# Sensor_HallArray_Ctrl.net
KiCad netlist of a schematic drawn in EAGLE
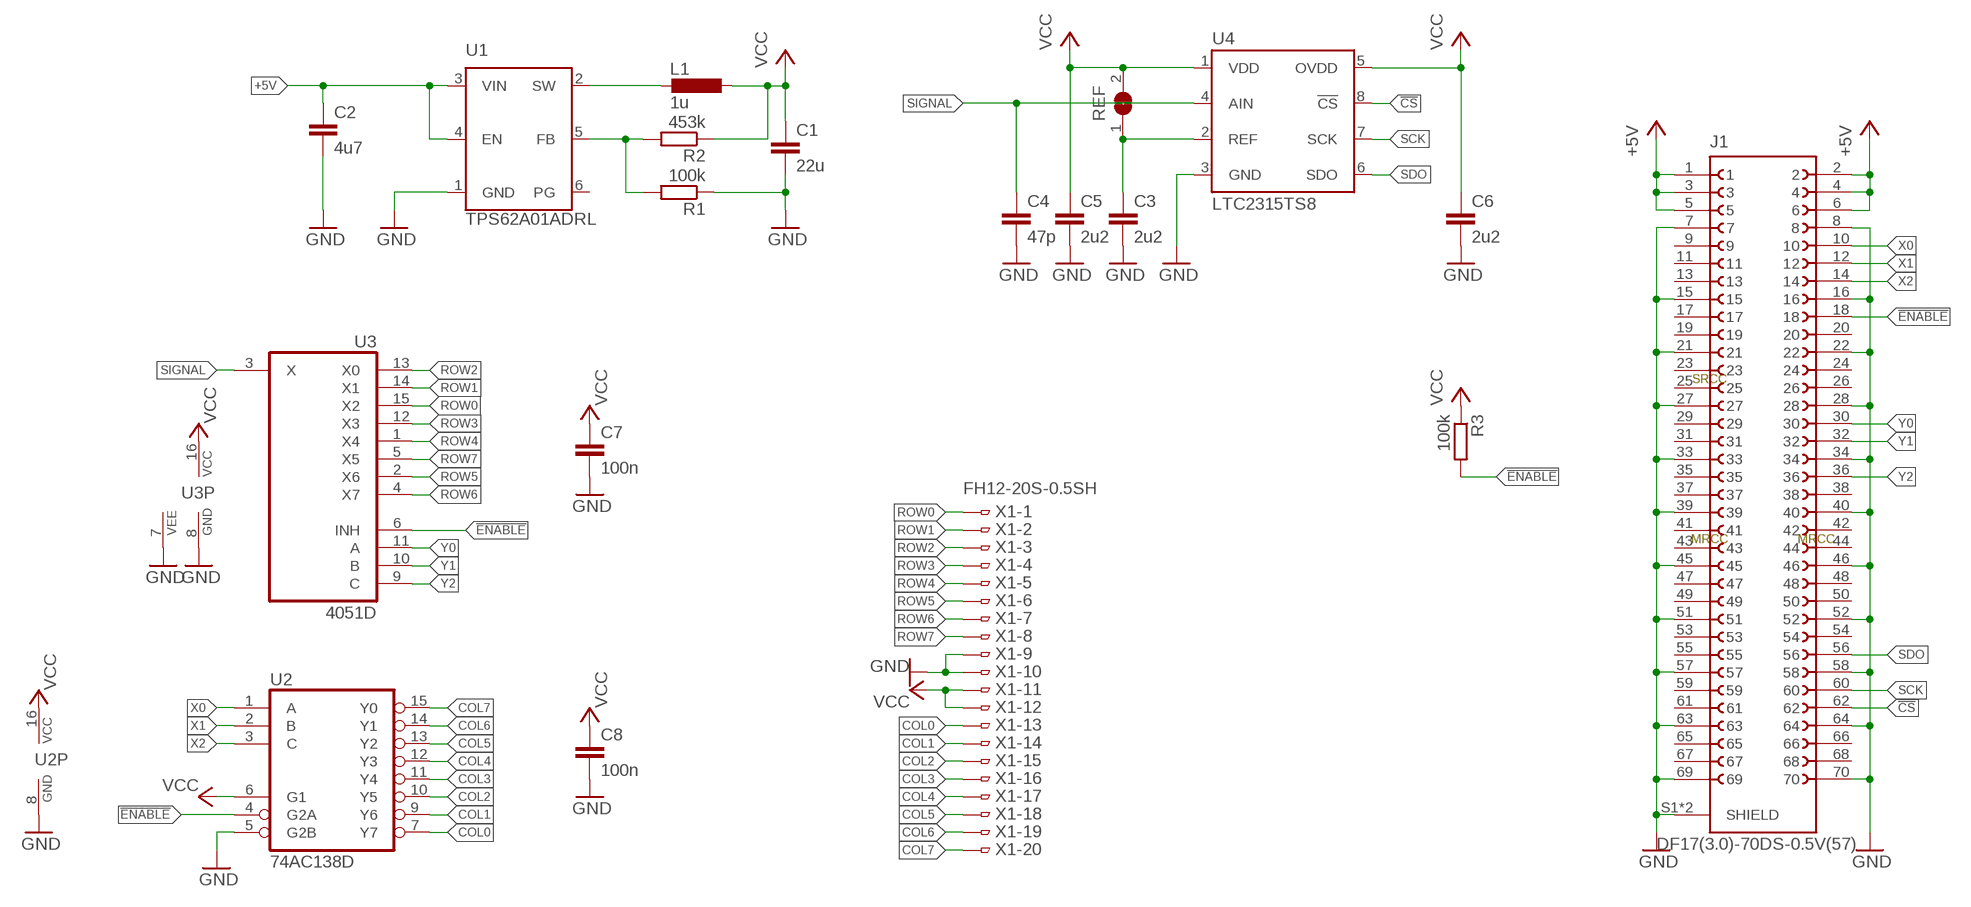
[diagram p0: schematic, sheet 1]

(export (version "E")
  (design (tool "Eeschema 10.0.6"))
  (components
    (comp (ref "C1")
      (value "22u")
      (footprint "eagle-import:C0603")
      (libsource (lib "eagle-import") (part "C-EUC0603"))
    )
    (comp (ref "C2")
      (value "4u7")
      (footprint "eagle-import:C0603")
      (libsource (lib "eagle-import") (part "C-EUC0603"))
    )
    (comp (ref "C3")
      (value "2u2")
      (footprint "eagle-import:C0603")
      (libsource (lib "eagle-import") (part "C-EUC0603"))
    )
    (comp (ref "C4")
      (value "47p")
      (footprint "eagle-import:C0402")
      (libsource (lib "eagle-import") (part "rcl_334_C-EUC0402"))
    )
    (comp (ref "C5")
      (value "2u2")
      (footprint "eagle-import:C0603")
      (libsource (lib "eagle-import") (part "C-EUC0603"))
    )
    (comp (ref "C6")
      (value "2u2")
      (footprint "eagle-import:C0603")
      (libsource (lib "eagle-import") (part "C-EUC0603"))
    )
    (comp (ref "C7")
      (value "100n")
      (footprint "eagle-import:C0402")
      (libsource (lib "eagle-import") (part "rcl_334_C-EUC0402"))
    )
    (comp (ref "C8")
      (value "100n")
      (footprint "eagle-import:C0402")
      (libsource (lib "eagle-import") (part "rcl_334_C-EUC0402"))
    )
    (comp (ref "J1")
      (value "DF17(3.0)-70DS-0.5V(57)")
      (footprint "eagle-import:DF17(3.0)-70DS-0.5V(57)")
      (libsource (lib "eagle-import") (part "DF17(3.0)-70DS-0.5V(57)"))
    )
    (comp (ref "L1")
      (value "1u")
      (footprint "eagle-import:L1008")
      (fields (field (name "MPN") "LQM2HPN1R0MG0L"))
      (libsource (lib "eagle-import") (part "L-EU1008"))
    )
    (comp (ref "R1")
      (value "100k")
      (footprint "eagle-import:R0402")
      (libsource (lib "eagle-import") (part "R-EU_R0402"))
    )
    (comp (ref "R2")
      (value "453k")
      (footprint "eagle-import:R0402")
      (libsource (lib "eagle-import") (part "R-EU_R0402"))
    )
    (comp (ref "R3")
      (value "100k")
      (footprint "eagle-import:R0402")
      (libsource (lib "eagle-import") (part "R-EU_R0402"))
    )
    (comp (ref "REF") (value "SJ") (footprint "eagle-import:SJ") (libsource (lib "eagle-import") (part "SJ")))
    (comp (ref "U1")
      (value "TPS62A01ADRL")
      (footprint "eagle-import:SOTFL50P160X60-6N")
      (fields (field (name "MANUFACTURER_PART_NUMBER") "TPS62A01ADRLR"))
      (libsource (lib "eagle-import") (part "TPS62A01ADRL"))
    )
    (comp (ref "U2")
      (value "74AC138D")
      (footprint "eagle-import:SO16")
      (libsource (lib "eagle-import") (part "74138DAC"))
    )
    (comp (ref "U3")
      (value "4051D")
      (footprint "eagle-import:SO16")
      (libsource (lib "eagle-import") (part "4051D"))
    )
    (comp (ref "U4")
      (value "LTC2315TS8")
      (footprint "eagle-import:SOT23-8L")
      (libsource (lib "eagle-import") (part "LTC2315TS8"))
    )
    (comp (ref "X1")
      (value "FH12-20S-0.5SH")
      (footprint "eagle-import:FH12-20S-0.5SH")
      (fields (field (name "MPN") "FH12-20S-0.5SH(55)"))
      (libsource (lib "eagle-import") (part "FH12-20S-0.5SH"))
    )
  )
  (nets
    (net (code "1") (name "+5V") (class "Default")
      (node (ref "C2") (pin "1") (pinfunction "1_1") (pintype "passive"))
      (node (ref "J1") (pin "1") (pinfunction "1_1") (pintype "passive"))
      (node (ref "J1") (pin "2") (pinfunction "2_2") (pintype "passive"))
      (node (ref "J1") (pin "3") (pinfunction "3_3") (pintype "passive"))
      (node (ref "J1") (pin "4") (pinfunction "4_4") (pintype "passive"))
      (node (ref "J1") (pin "5") (pinfunction "5_5") (pintype "passive"))
      (node (ref "J1") (pin "6") (pinfunction "6_6") (pintype "passive"))
      (node (ref "U1") (pin "3") (pinfunction "VIN_3") (pintype "bidirectional"))
      (node (ref "U1") (pin "4") (pinfunction "EN_4") (pintype "bidirectional"))
    )
    (net (code "2") (name "/~{CS}") (class "Default")
      (node (ref "J1") (pin "62") (pinfunction "62_62") (pintype "passive"))
      (node (ref "U4") (pin "8") (pinfunction "~{CS}_8") (pintype "input"))
    )
    (net (code "3") (name "/~{ENABLE}") (class "Default")
      (node (ref "J1") (pin "18") (pinfunction "18_18") (pintype "passive"))
      (node (ref "R3") (pin "2") (pinfunction "2_2") (pintype "passive"))
      (node (ref "U2") (pin "4") (pinfunction "G2A_4") (pintype "input"))
      (node (ref "U3") (pin "6") (pinfunction "INH_6") (pintype "input"))
    )
    (net (code "4") (name "COL0") (class "Default")
      (node (ref "U2") (pin "7") (pinfunction "Y7_7") (pintype "output"))
      (node (ref "X1") (pin "13") (pinfunction "1_13") (pintype "passive"))
    )
    (net (code "5") (name "COL1") (class "Default")
      (node (ref "U2") (pin "9") (pinfunction "Y6_9") (pintype "output"))
      (node (ref "X1") (pin "14") (pinfunction "1_14") (pintype "passive"))
    )
    (net (code "6") (name "COL2") (class "Default")
      (node (ref "U2") (pin "10") (pinfunction "Y5_10") (pintype "output"))
      (node (ref "X1") (pin "15") (pinfunction "1_15") (pintype "passive"))
    )
    (net (code "7") (name "COL3") (class "Default")
      (node (ref "U2") (pin "11") (pinfunction "Y4_11") (pintype "output"))
      (node (ref "X1") (pin "16") (pinfunction "1_16") (pintype "passive"))
    )
    (net (code "8") (name "COL4") (class "Default")
      (node (ref "U2") (pin "12") (pinfunction "Y3_12") (pintype "output"))
      (node (ref "X1") (pin "17") (pinfunction "1_17") (pintype "passive"))
    )
    (net (code "9") (name "COL5") (class "Default")
      (node (ref "U2") (pin "13") (pinfunction "Y2_13") (pintype "output"))
      (node (ref "X1") (pin "18") (pinfunction "1_18") (pintype "passive"))
    )
    (net (code "10") (name "COL6") (class "Default")
      (node (ref "U2") (pin "14") (pinfunction "Y1_14") (pintype "output"))
      (node (ref "X1") (pin "19") (pinfunction "1_19") (pintype "passive"))
    )
    (net (code "11") (name "COL7") (class "Default")
      (node (ref "U2") (pin "15") (pinfunction "Y0_15") (pintype "output"))
      (node (ref "X1") (pin "20") (pinfunction "1_20") (pintype "passive"))
    )
    (net (code "12") (name "GND") (class "Default")
      (node (ref "C1") (pin "2") (pinfunction "2_2") (pintype "passive"))
      (node (ref "C2") (pin "2") (pinfunction "2_2") (pintype "passive"))
      (node (ref "C3") (pin "2") (pinfunction "2_2") (pintype "passive"))
      (node (ref "C4") (pin "2") (pinfunction "2_2") (pintype "passive"))
      (node (ref "C5") (pin "2") (pinfunction "2_2") (pintype "passive"))
      (node (ref "C6") (pin "2") (pinfunction "2_2") (pintype "passive"))
      (node (ref "C7") (pin "2") (pinfunction "2_2") (pintype "passive"))
      (node (ref "C8") (pin "2") (pinfunction "2_2") (pintype "passive"))
      (node (ref "J1") (pin "15") (pinfunction "15_15") (pintype "passive"))
      (node (ref "J1") (pin "16") (pinfunction "16_16") (pintype "passive"))
      (node (ref "J1") (pin "21") (pinfunction "21_21") (pintype "passive"))
      (node (ref "J1") (pin "22") (pinfunction "22_22") (pintype "passive"))
      (node (ref "J1") (pin "27") (pinfunction "27_27") (pintype "passive"))
      (node (ref "J1") (pin "28") (pinfunction "28_28") (pintype "passive"))
      (node (ref "J1") (pin "33") (pinfunction "33_33") (pintype "passive"))
      (node (ref "J1") (pin "34") (pinfunction "34_34") (pintype "passive"))
      (node (ref "J1") (pin "39") (pinfunction "39_39") (pintype "passive"))
      (node (ref "J1") (pin "40") (pinfunction "40_40") (pintype "passive"))
      (node (ref "J1") (pin "45") (pinfunction "45_45") (pintype "passive"))
      (node (ref "J1") (pin "46") (pinfunction "46_46") (pintype "passive"))
      (node (ref "J1") (pin "51") (pinfunction "51_51") (pintype "passive"))
      (node (ref "J1") (pin "52") (pinfunction "52_52") (pintype "passive"))
      (node (ref "J1") (pin "57") (pinfunction "57_57") (pintype "passive"))
      (node (ref "J1") (pin "58") (pinfunction "58_58") (pintype "passive"))
      (node (ref "J1") (pin "63") (pinfunction "63_63") (pintype "passive"))
      (node (ref "J1") (pin "64") (pinfunction "64_64") (pintype "passive"))
      (node (ref "J1") (pin "69") (pinfunction "69_69") (pintype "passive"))
      (node (ref "J1") (pin "7") (pinfunction "7_7") (pintype "passive"))
      (node (ref "J1") (pin "70") (pinfunction "70_70") (pintype "passive"))
      (node (ref "J1") (pin "8") (pinfunction "8_8") (pintype "passive"))
      (node (ref "J1") (pin "S1") (pinfunction "SHIELD_S1") (pintype "passive"))
      (node (ref "J1") (pin "S2") (pinfunction "SHIELD_S2") (pintype "passive"))
      (node (ref "R1") (pin "1") (pinfunction "1_1") (pintype "passive"))
      (node (ref "U1") (pin "1") (pinfunction "GND_1") (pintype "bidirectional"))
      (node (ref "U2") (pin "5") (pinfunction "G2B_5") (pintype "input"))
      (node (ref "U2") (pin "8") (pinfunction "GND_8") (pintype "power_in"))
      (node (ref "U3") (pin "7") (pinfunction "VEE_7") (pintype "power_in"))
      (node (ref "U3") (pin "8") (pinfunction "GND_8") (pintype "power_in"))
      (node (ref "U4") (pin "3") (pinfunction "GND_3") (pintype "power_in"))
      (node (ref "X1") (pin "10") (pinfunction "1_10") (pintype "passive"))
      (node (ref "X1") (pin "9") (pinfunction "1_9") (pintype "passive"))
    )
    (net (code "13") (name "Net-(U1-FB)") (class "Default")
      (node (ref "R1") (pin "2") (pinfunction "2_2") (pintype "passive"))
      (node (ref "R2") (pin "2") (pinfunction "2_2") (pintype "passive"))
      (node (ref "U1") (pin "5") (pinfunction "FB_5") (pintype "bidirectional"))
    )
    (net (code "14") (name "Net-(U1-SW)") (class "Default")
      (node (ref "L1") (pin "2") (pinfunction "2_2") (pintype "passive"))
      (node (ref "U1") (pin "2") (pinfunction "SW_2") (pintype "bidirectional"))
    )
    (net (code "15") (name "Net-(U4-REF)") (class "Default")
      (node (ref "C3") (pin "1") (pinfunction "1_1") (pintype "passive"))
      (node (ref "REF") (pin "1") (pinfunction "1_1") (pintype "passive"))
      (node (ref "U4") (pin "2") (pinfunction "REF_2") (pintype "input"))
    )
    (net (code "16") (name "ROW0") (class "Default")
      (node (ref "U3") (pin "15") (pinfunction "X2_15") (pintype "bidirectional"))
      (node (ref "X1") (pin "1") (pinfunction "1_1") (pintype "passive"))
    )
    (net (code "17") (name "ROW1") (class "Default")
      (node (ref "U3") (pin "14") (pinfunction "X1_14") (pintype "bidirectional"))
      (node (ref "X1") (pin "2") (pinfunction "1_2") (pintype "passive"))
    )
    (net (code "18") (name "ROW2") (class "Default")
      (node (ref "U3") (pin "13") (pinfunction "X0_13") (pintype "bidirectional"))
      (node (ref "X1") (pin "3") (pinfunction "1_3") (pintype "passive"))
    )
    (net (code "19") (name "ROW3") (class "Default")
      (node (ref "U3") (pin "12") (pinfunction "X3_12") (pintype "bidirectional"))
      (node (ref "X1") (pin "4") (pinfunction "1_4") (pintype "passive"))
    )
    (net (code "20") (name "ROW4") (class "Default")
      (node (ref "U3") (pin "1") (pinfunction "X4_1") (pintype "bidirectional"))
      (node (ref "X1") (pin "5") (pinfunction "1_5") (pintype "passive"))
    )
    (net (code "21") (name "ROW5") (class "Default")
      (node (ref "U3") (pin "2") (pinfunction "X6_2") (pintype "bidirectional"))
      (node (ref "X1") (pin "6") (pinfunction "1_6") (pintype "passive"))
    )
    (net (code "22") (name "ROW6") (class "Default")
      (node (ref "U3") (pin "4") (pinfunction "X7_4") (pintype "bidirectional"))
      (node (ref "X1") (pin "7") (pinfunction "1_7") (pintype "passive"))
    )
    (net (code "23") (name "ROW7") (class "Default")
      (node (ref "U3") (pin "5") (pinfunction "X5_5") (pintype "bidirectional"))
      (node (ref "X1") (pin "8") (pinfunction "1_8") (pintype "passive"))
    )
    (net (code "24") (name "SCK") (class "Default")
      (node (ref "J1") (pin "60") (pinfunction "60_60") (pintype "passive"))
      (node (ref "U4") (pin "7") (pinfunction "SCK_7") (pintype "input"))
    )
    (net (code "25") (name "SDO") (class "Default")
      (node (ref "J1") (pin "56") (pinfunction "56_56") (pintype "passive"))
      (node (ref "U4") (pin "6") (pinfunction "SDO_6") (pintype "output"))
    )
    (net (code "26") (name "SIGNAL") (class "Default")
      (node (ref "C4") (pin "1") (pinfunction "1_1") (pintype "passive"))
      (node (ref "U3") (pin "3") (pinfunction "X_3") (pintype "bidirectional"))
      (node (ref "U4") (pin "4") (pinfunction "AIN_4") (pintype "input"))
    )
    (net (code "27") (name "VCC") (class "Default")
      (node (ref "C1") (pin "1") (pinfunction "1_1") (pintype "passive"))
      (node (ref "C5") (pin "1") (pinfunction "1_1") (pintype "passive"))
      (node (ref "C6") (pin "1") (pinfunction "1_1") (pintype "passive"))
      (node (ref "C7") (pin "1") (pinfunction "1_1") (pintype "passive"))
      (node (ref "C8") (pin "1") (pinfunction "1_1") (pintype "passive"))
      (node (ref "L1") (pin "1") (pinfunction "1_1") (pintype "passive"))
      (node (ref "R2") (pin "1") (pinfunction "1_1") (pintype "passive"))
      (node (ref "R3") (pin "1") (pinfunction "1_1") (pintype "passive"))
      (node (ref "REF") (pin "2") (pinfunction "2_2") (pintype "passive"))
      (node (ref "U2") (pin "16") (pinfunction "VCC_16") (pintype "power_in"))
      (node (ref "U2") (pin "6") (pinfunction "G1_6") (pintype "input"))
      (node (ref "U3") (pin "16") (pinfunction "VCC_16") (pintype "power_in"))
      (node (ref "U4") (pin "1") (pinfunction "VDD_1") (pintype "power_in"))
      (node (ref "U4") (pin "5") (pinfunction "OVDD_5") (pintype "power_in"))
      (node (ref "X1") (pin "11") (pinfunction "1_11") (pintype "passive"))
      (node (ref "X1") (pin "12") (pinfunction "1_12") (pintype "passive"))
    )
    (net (code "28") (name "X0") (class "Default")
      (node (ref "J1") (pin "10") (pinfunction "10_10") (pintype "passive"))
      (node (ref "U2") (pin "1") (pinfunction "A_1") (pintype "input"))
    )
    (net (code "29") (name "X1") (class "Default")
      (node (ref "J1") (pin "12") (pinfunction "12_12") (pintype "passive"))
      (node (ref "U2") (pin "2") (pinfunction "B_2") (pintype "input"))
    )
    (net (code "30") (name "X2") (class "Default")
      (node (ref "J1") (pin "14") (pinfunction "14_14") (pintype "passive"))
      (node (ref "U2") (pin "3") (pinfunction "C_3") (pintype "input"))
    )
    (net (code "31") (name "Y0") (class "Default")
      (node (ref "J1") (pin "30") (pinfunction "30_30") (pintype "passive"))
      (node (ref "U3") (pin "11") (pinfunction "A_11") (pintype "input"))
    )
    (net (code "32") (name "Y1") (class "Default")
      (node (ref "J1") (pin "32") (pinfunction "32_32") (pintype "passive"))
      (node (ref "U3") (pin "10") (pinfunction "B_10") (pintype "input"))
    )
    (net (code "33") (name "Y2") (class "Default")
      (node (ref "J1") (pin "36") (pinfunction "36_36") (pintype "passive"))
      (node (ref "U3") (pin "9") (pinfunction "C_9") (pintype "input"))
    )
    (net (code "34") (name "unconnected-(J1-Pad9)") (class "Default")
      (node (ref "J1") (pin "9") (pinfunction "9_9") (pintype "passive"))
    )
    (net (code "35") (name "unconnected-(J1-Pad11)") (class "Default")
      (node (ref "J1") (pin "11") (pinfunction "11_11") (pintype "passive"))
    )
    (net (code "36") (name "unconnected-(J1-Pad13)") (class "Default")
      (node (ref "J1") (pin "13") (pinfunction "13_13") (pintype "passive"))
    )
    (net (code "37") (name "unconnected-(J1-Pad17)") (class "Default")
      (node (ref "J1") (pin "17") (pinfunction "17_17") (pintype "passive"))
    )
    (net (code "38") (name "unconnected-(J1-Pad19)") (class "Default")
      (node (ref "J1") (pin "19") (pinfunction "19_19") (pintype "passive"))
    )
    (net (code "39") (name "unconnected-(J1-Pad20)") (class "Default")
      (node (ref "J1") (pin "20") (pinfunction "20_20") (pintype "passive"))
    )
    (net (code "40") (name "unconnected-(J1-Pad23)") (class "Default")
      (node (ref "J1") (pin "23") (pinfunction "23_23") (pintype "passive"))
    )
    (net (code "41") (name "unconnected-(J1-Pad24)") (class "Default")
      (node (ref "J1") (pin "24") (pinfunction "24_24") (pintype "passive"))
    )
    (net (code "42") (name "unconnected-(J1-Pad25)") (class "Default")
      (node (ref "J1") (pin "25") (pinfunction "25_25") (pintype "passive"))
    )
    (net (code "43") (name "unconnected-(J1-Pad26)") (class "Default")
      (node (ref "J1") (pin "26") (pinfunction "26_26") (pintype "passive"))
    )
    (net (code "44") (name "unconnected-(J1-Pad29)") (class "Default")
      (node (ref "J1") (pin "29") (pinfunction "29_29") (pintype "passive"))
    )
    (net (code "45") (name "unconnected-(J1-Pad31)") (class "Default")
      (node (ref "J1") (pin "31") (pinfunction "31_31") (pintype "passive"))
    )
    (net (code "46") (name "unconnected-(J1-Pad35)") (class "Default")
      (node (ref "J1") (pin "35") (pinfunction "35_35") (pintype "passive"))
    )
    (net (code "47") (name "unconnected-(J1-Pad37)") (class "Default")
      (node (ref "J1") (pin "37") (pinfunction "37_37") (pintype "passive"))
    )
    (net (code "48") (name "unconnected-(J1-Pad38)") (class "Default")
      (node (ref "J1") (pin "38") (pinfunction "38_38") (pintype "passive"))
    )
    (net (code "49") (name "unconnected-(J1-Pad41)") (class "Default")
      (node (ref "J1") (pin "41") (pinfunction "41_41") (pintype "passive"))
    )
    (net (code "50") (name "unconnected-(J1-Pad42)") (class "Default")
      (node (ref "J1") (pin "42") (pinfunction "42_42") (pintype "passive"))
    )
    (net (code "51") (name "unconnected-(J1-Pad43)") (class "Default")
      (node (ref "J1") (pin "43") (pinfunction "43_43") (pintype "passive"))
    )
    (net (code "52") (name "unconnected-(J1-Pad44)") (class "Default")
      (node (ref "J1") (pin "44") (pinfunction "44_44") (pintype "passive"))
    )
    (net (code "53") (name "unconnected-(J1-Pad47)") (class "Default")
      (node (ref "J1") (pin "47") (pinfunction "47_47") (pintype "passive"))
    )
    (net (code "54") (name "unconnected-(J1-Pad48)") (class "Default")
      (node (ref "J1") (pin "48") (pinfunction "48_48") (pintype "passive"))
    )
    (net (code "55") (name "unconnected-(J1-Pad49)") (class "Default")
      (node (ref "J1") (pin "49") (pinfunction "49_49") (pintype "passive"))
    )
    (net (code "56") (name "unconnected-(J1-Pad50)") (class "Default")
      (node (ref "J1") (pin "50") (pinfunction "50_50") (pintype "passive"))
    )
    (net (code "57") (name "unconnected-(J1-Pad53)") (class "Default")
      (node (ref "J1") (pin "53") (pinfunction "53_53") (pintype "passive"))
    )
    (net (code "58") (name "unconnected-(J1-Pad54)") (class "Default")
      (node (ref "J1") (pin "54") (pinfunction "54_54") (pintype "passive"))
    )
    (net (code "59") (name "unconnected-(J1-Pad55)") (class "Default")
      (node (ref "J1") (pin "55") (pinfunction "55_55") (pintype "passive"))
    )
    (net (code "60") (name "unconnected-(J1-Pad59)") (class "Default")
      (node (ref "J1") (pin "59") (pinfunction "59_59") (pintype "passive"))
    )
    (net (code "61") (name "unconnected-(J1-Pad61)") (class "Default")
      (node (ref "J1") (pin "61") (pinfunction "61_61") (pintype "passive"))
    )
    (net (code "62") (name "unconnected-(J1-Pad65)") (class "Default")
      (node (ref "J1") (pin "65") (pinfunction "65_65") (pintype "passive"))
    )
    (net (code "63") (name "unconnected-(J1-Pad66)") (class "Default")
      (node (ref "J1") (pin "66") (pinfunction "66_66") (pintype "passive"))
    )
    (net (code "64") (name "unconnected-(J1-Pad67)") (class "Default")
      (node (ref "J1") (pin "67") (pinfunction "67_67") (pintype "passive"))
    )
    (net (code "65") (name "unconnected-(J1-Pad68)") (class "Default")
      (node (ref "J1") (pin "68") (pinfunction "68_68") (pintype "passive"))
    )
    (net (code "66") (name "unconnected-(U1-PG-Pad6)") (class "Default")
      (node (ref "U1") (pin "6") (pinfunction "PG_6") (pintype "bidirectional"))
    )
  )
)
